# 8_Halleffect.net
KiCad netlist of a schematic drawn in Altium Designer
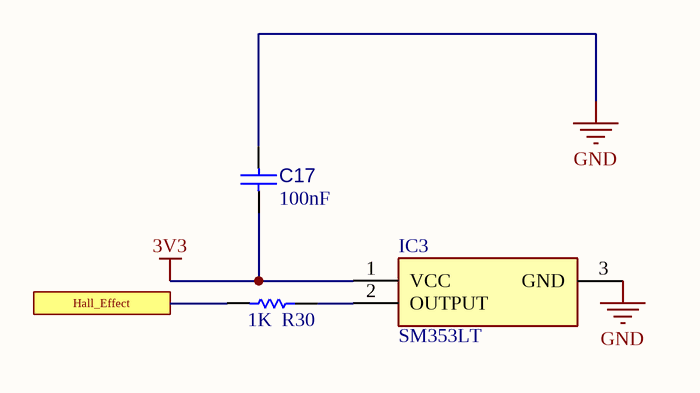
[diagram p0: [8]Halleffect.SchDoc]

(export (version "E")
  (design (tool "Eeschema 10.0.6"))
  (components
    (comp (ref "C17")
      (value "100nF")
      (footprint "CAPC1608X90X40ML10T20")
      (description "Chip Capacitor, 100 nF, +/- 10%, 50 V, 0603 (1608 Metric)")
      (fields (field (name "TOLERANCE") "10%") (field (name "Comment") "Capacitor 100 nF +/-10% 50 V 0603"))
      (libsource (lib "Latium Technologies") (part "CAP-NP-2"))
    )
    (comp (ref "IC3")
      (value "SM353LT")
      (footprint "SOT95P280X145-3N")
      (description "Integrated Circuit")
      (fields (field (name "MOUSER PART NUMBER") "785-SM353LT"))
      (libsource (lib "PCB_High_Voltage_Sensor") (part "SM353LT"))
    )
    (comp (ref "R30")
      (value "1K")
      (footprint "RES 0603")
      (description "1K 1% 0.1W [0603]")
      (fields (field (name "TOLERANCE") "1%"))
      (libsource (lib "MasterLib") (part "RES 3.3M 1% 0.1W [0603]"))
    )
  )
  (nets
    (net (code "1") (name "/Hall_Effect") (class "Default")
      (node (ref "R30") (pin "2") (pinfunction "2_2") (pintype "passive"))
    )
    (net (code "2") (name "3V3") (class "Default")
      (node (ref "C17") (pin "1") (pinfunction "1_1") (pintype "passive"))
      (node (ref "IC3") (pin "1") (pinfunction "VCC_1") (pintype "passive"))
    )
    (net (code "3") (name "GND") (class "Default")
      (node (ref "C17") (pin "2") (pinfunction "2_2") (pintype "passive"))
      (node (ref "IC3") (pin "3") (pinfunction "GND_3") (pintype "passive"))
    )
    (net (code "4") (name "Net-(IC3-OUTPUT)") (class "Default")
      (node (ref "IC3") (pin "2") (pinfunction "OUTPUT_2") (pintype "passive"))
      (node (ref "R30") (pin "1") (pinfunction "1_1") (pintype "passive"))
    )
  )
)
